# POEActiveTransformer.net
KiCad netlist of a schematic drawn in Altium Designer
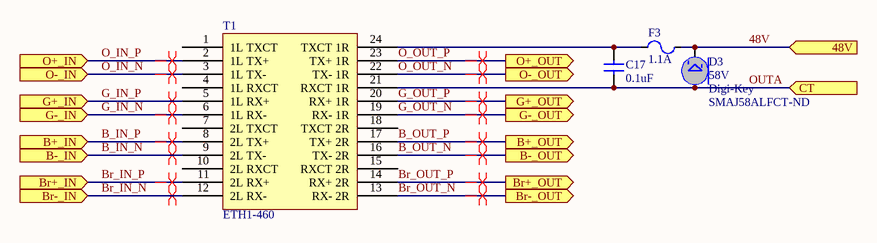
[diagram p0: POEActiveTransformer.SchDoc]

(export (version "E")
  (design (tool "Eeschema 10.0.6"))
  (components
    (comp (ref "C17")
      (value "0.1uF")
      (footprint "CAPC0603")
      (fields (field (name "Comment") "Cap"))
      (libsource (lib "Passives") (part "Cap"))
    )
    (comp (ref "D3")
      (value "58V")
      (footprint "SMASeries")
      (description "Zener Diode")
      (fields
        (field (name "SUPPLIER 1") "Digi-Key")
        (field (name "SUPPLIER PART NUMBER 1") "SMAJ58ALFCT-ND")
        (field (name "Comment") "Zener")
      )
      (libsource (lib "Semiconductors") (part "Zener"))
    )
    (comp (ref "F3")
      (value "1.1A")
      (footprint "PTC7451X11N")
      (fields (field (name "Comment") "PTC Fuse"))
      (libsource (lib "Passives") (part "PTC_Fuse"))
    )
    (comp (ref "T1")
      (value "ETH1-460")
      (footprint "ETH1-460")
      (description "\"PoE Plus\" Transformers Audio & Signal ETH1 60W 4pairs PoE+ Magnetic Module")
      (libsource (lib "ICs") (part "ETH1-460"))
    )
  )
  (nets
    (net (code "1") (name "/48V") (class "Default")
      (node (ref "D3") (pin "C") (pinfunction "C_C") (pintype "passive"))
      (node (ref "F3") (pin "2") (pinfunction "B_2") (pintype "passive"))
    )
    (net (code "2") (name "/B_IN_N") (class "Default")
      (node (ref "T1") (pin "9") (pinfunction "2L_TX-_9") (pintype "passive"))
    )
    (net (code "3") (name "/B_IN_P") (class "Default")
      (node (ref "T1") (pin "8") (pinfunction "2L_TX+_8") (pintype "passive"))
    )
    (net (code "4") (name "/B_OUT_N") (class "Default")
      (node (ref "T1") (pin "16") (pinfunction "TX-_2R_16") (pintype "passive"))
    )
    (net (code "5") (name "/B_OUT_P") (class "Default")
      (node (ref "T1") (pin "17") (pinfunction "TX+_2R_17") (pintype "passive"))
    )
    (net (code "6") (name "/Br_IN_N") (class "Default")
      (node (ref "T1") (pin "12") (pinfunction "2L_RX-_12") (pintype "passive"))
    )
    (net (code "7") (name "/Br_IN_P") (class "Default")
      (node (ref "T1") (pin "11") (pinfunction "2L_RX+_11") (pintype "passive"))
    )
    (net (code "8") (name "/Br_OUT_N") (class "Default")
      (node (ref "T1") (pin "13") (pinfunction "RX-_2R_13") (pintype "passive"))
    )
    (net (code "9") (name "/Br_OUT_P") (class "Default")
      (node (ref "T1") (pin "14") (pinfunction "RX+_2R_14") (pintype "passive"))
    )
    (net (code "10") (name "/G_IN_N") (class "Default")
      (node (ref "T1") (pin "6") (pinfunction "1L_RX-_6") (pintype "passive"))
    )
    (net (code "11") (name "/G_IN_P") (class "Default")
      (node (ref "T1") (pin "5") (pinfunction "1L_RX+_5") (pintype "passive"))
    )
    (net (code "12") (name "/G_OUT_N") (class "Default")
      (node (ref "T1") (pin "19") (pinfunction "RX-_1R_19") (pintype "passive"))
    )
    (net (code "13") (name "/G_OUT_P") (class "Default")
      (node (ref "T1") (pin "20") (pinfunction "RX+_1R_20") (pintype "passive"))
    )
    (net (code "14") (name "/OUTA") (class "Default")
      (node (ref "C17") (pin "2") (pinfunction "B_2") (pintype "passive"))
      (node (ref "D3") (pin "A") (pinfunction "A_A") (pintype "passive"))
      (node (ref "T1") (pin "21") (pinfunction "RXCT_1R_21") (pintype "passive"))
    )
    (net (code "15") (name "/O_IN_N") (class "Default")
      (node (ref "T1") (pin "3") (pinfunction "1L_TX-_3") (pintype "passive"))
    )
    (net (code "16") (name "/O_IN_P") (class "Default")
      (node (ref "T1") (pin "2") (pinfunction "1L_TX+_2") (pintype "passive"))
    )
    (net (code "17") (name "/O_OUT_N") (class "Default")
      (node (ref "T1") (pin "22") (pinfunction "TX-_1R_22") (pintype "passive"))
    )
    (net (code "18") (name "/O_OUT_P") (class "Default")
      (node (ref "T1") (pin "23") (pinfunction "TX+_1R_23") (pintype "passive"))
    )
    (net (code "19") (name "Net-(C17-A)") (class "Default")
      (node (ref "C17") (pin "1") (pinfunction "A_1") (pintype "passive"))
      (node (ref "F3") (pin "1") (pinfunction "A_1") (pintype "passive"))
      (node (ref "T1") (pin "24") (pinfunction "TXCT_1R_24") (pintype "passive"))
    )
    (net (code "20") (name "unconnected-(T1-1L_RXCT-Pad4)") (class "Default")
      (node (ref "T1") (pin "4") (pinfunction "1L_RXCT_4") (pintype "passive"))
    )
    (net (code "21") (name "unconnected-(T1-1L_TXCT-Pad1)") (class "Default")
      (node (ref "T1") (pin "1") (pinfunction "1L_TXCT_1") (pintype "passive"))
    )
    (net (code "22") (name "unconnected-(T1-2L_RXCT-Pad10)") (class "Default")
      (node (ref "T1") (pin "10") (pinfunction "2L_RXCT_10") (pintype "passive"))
    )
    (net (code "23") (name "unconnected-(T1-2L_TXCT-Pad7)") (class "Default")
      (node (ref "T1") (pin "7") (pinfunction "2L_TXCT_7") (pintype "passive"))
    )
    (net (code "24") (name "unconnected-(T1-RXCT_2R-Pad15)") (class "Default")
      (node (ref "T1") (pin "15") (pinfunction "RXCT_2R_15") (pintype "passive"))
    )
    (net (code "25") (name "unconnected-(T1-TXCT_2R-Pad18)") (class "Default")
      (node (ref "T1") (pin "18") (pinfunction "TXCT_2R_18") (pintype "passive"))
    )
  )
)
